# BMS_BatteryThermistors.net
KiCad netlist of a schematic drawn in Altium Designer
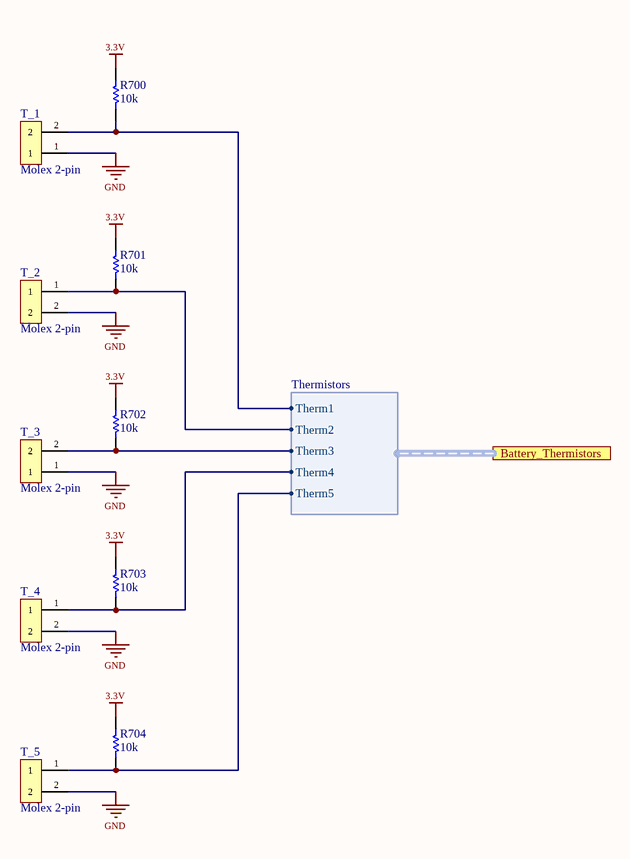
[diagram p0: BMS_BatteryThermistors.SchDoc]

(export (version "E")
  (design (tool "Eeschema 10.0.6"))
  (components
    (comp (ref "R700")
      (value "10k")
      (footprint "RESC2012X07N")
      (description "Resistor")
      (fields (field (name "Comment") "R0805") (field (name "PUBLISHER") "Altium Limited"))
      (libsource (lib "Miscellaneous Devices") (part "Res1"))
    )
    (comp (ref "R701")
      (value "10k")
      (footprint "RESC2012X07N")
      (description "Resistor")
      (fields (field (name "Comment") "R0805") (field (name "PUBLISHER") "Altium Limited"))
      (libsource (lib "Miscellaneous Devices") (part "Res1"))
    )
    (comp (ref "R702")
      (value "10k")
      (footprint "RESC2012X07N")
      (description "Resistor")
      (fields (field (name "Comment") "R0805") (field (name "PUBLISHER") "Altium Limited"))
      (libsource (lib "Miscellaneous Devices") (part "Res1"))
    )
    (comp (ref "R703")
      (value "10k")
      (footprint "RESC2012X07N")
      (description "Resistor")
      (fields (field (name "Comment") "R0805") (field (name "PUBLISHER") "Altium Limited"))
      (libsource (lib "Miscellaneous Devices") (part "Res1"))
    )
    (comp (ref "R704")
      (value "10k")
      (footprint "RESC2012X07N")
      (description "Resistor")
      (fields (field (name "Comment") "R0805") (field (name "PUBLISHER") "Altium Limited"))
      (libsource (lib "Miscellaneous Devices") (part "Res1"))
    )
    (comp (ref "T_1")
      (value "Molex 2-pin")
      (footprint "ThermistorConnector")
      (libsource (lib "Molex 2-pin") (part "Molex 2-pin"))
    )
    (comp (ref "T_2")
      (value "Molex 2-pin")
      (footprint "ThermistorConnector")
      (libsource (lib "") (part "Molex 2-pin_1"))
    )
    (comp (ref "T_3")
      (value "Molex 2-pin")
      (footprint "ThermistorConnector")
      (libsource (lib "Molex 2-pin") (part "Molex 2-pin"))
    )
    (comp (ref "T_4")
      (value "Molex 2-pin")
      (footprint "ThermistorConnector")
      (libsource (lib "") (part "Molex 2-pin_1"))
    )
    (comp (ref "T_5")
      (value "Molex 2-pin")
      (footprint "ThermistorConnector")
      (libsource (lib "") (part "Molex 2-pin_1"))
    )
  )
  (nets
    (net (code "3") (name "3.3V") (class "Default")
      (node (ref "R700") (pin "2") (pinfunction "2_2") (pintype "passive"))
      (node (ref "R701") (pin "2") (pinfunction "2_2") (pintype "passive"))
      (node (ref "R702") (pin "2") (pinfunction "2_2") (pintype "passive"))
      (node (ref "R703") (pin "2") (pinfunction "2_2") (pintype "passive"))
      (node (ref "R704") (pin "2") (pinfunction "2_2") (pintype "passive"))
    )
    (net (code "4") (name "GND") (class "Default")
      (node (ref "T_1") (pin "1") (pinfunction "1_1") (pintype "passive"))
      (node (ref "T_2") (pin "2") (pinfunction "2_2") (pintype "passive"))
      (node (ref "T_3") (pin "1") (pinfunction "1_1") (pintype "passive"))
      (node (ref "T_4") (pin "2") (pinfunction "2_2") (pintype "passive"))
      (node (ref "T_5") (pin "2") (pinfunction "2_2") (pintype "passive"))
    )
    (net (code "5") (name "Net-(R700-Pad1)") (class "Default")
      (node (ref "R700") (pin "1") (pinfunction "1_1") (pintype "passive"))
      (node (ref "T_1") (pin "2") (pinfunction "2_2") (pintype "passive"))
    )
    (net (code "6") (name "Net-(R701-Pad1)") (class "Default")
      (node (ref "R701") (pin "1") (pinfunction "1_1") (pintype "passive"))
      (node (ref "T_2") (pin "1") (pinfunction "1_1") (pintype "passive"))
    )
    (net (code "7") (name "Net-(R702-Pad1)") (class "Default")
      (node (ref "R702") (pin "1") (pinfunction "1_1") (pintype "passive"))
      (node (ref "T_3") (pin "2") (pinfunction "2_2") (pintype "passive"))
    )
    (net (code "8") (name "Net-(R703-Pad1)") (class "Default")
      (node (ref "R703") (pin "1") (pinfunction "1_1") (pintype "passive"))
      (node (ref "T_4") (pin "1") (pinfunction "1_1") (pintype "passive"))
    )
    (net (code "9") (name "Net-(R704-Pad1)") (class "Default")
      (node (ref "R704") (pin "1") (pinfunction "1_1") (pintype "passive"))
      (node (ref "T_5") (pin "1") (pinfunction "1_1") (pintype "passive"))
    )
  )
)
